# SD_card.net
KiCad netlist of a schematic drawn in Altium Designer
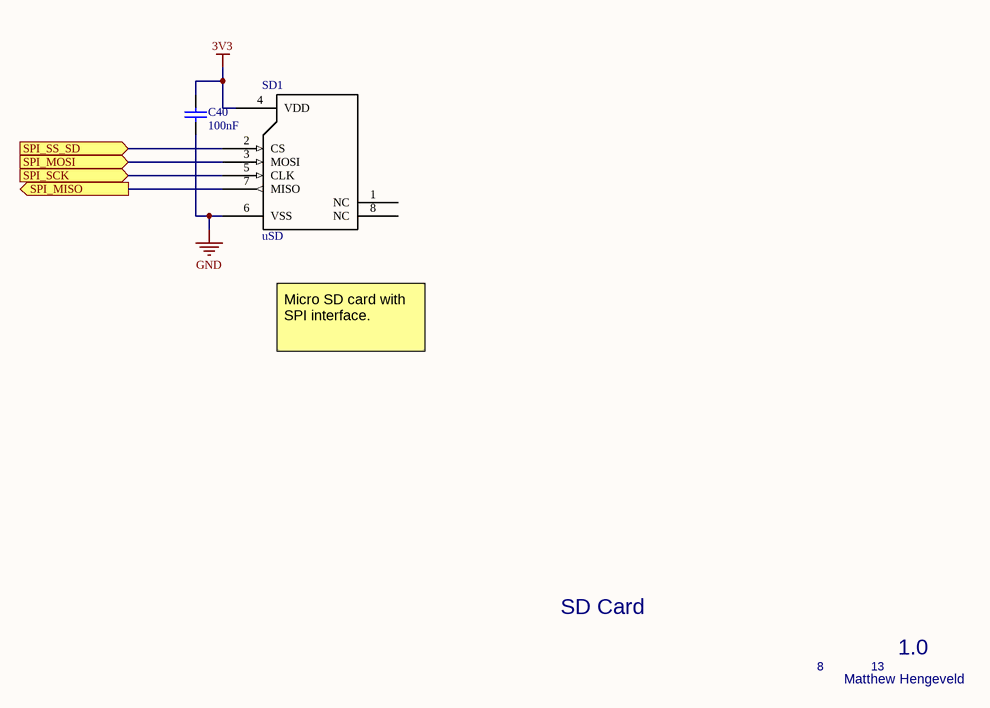
[diagram p0: SD card.SchDoc]

(export (version "E")
  (design (tool "Eeschema 10.0.6"))
  (components
    (comp (ref "C40")
      (value "100nF")
      (footprint "CAPC1608X92X38LL15T08")
      (fields (field (name "PART NUMBER") "VJ0603Y104KNXAO") (field (name "MANUFACTURER") "Vitramon"))
      (libsource (lib "Altium Content Vault") (part "CAP"))
    )
    (comp (ref "SD1")
      (value "uSD")
      (footprint "uSD")
      (description "uSD Card Holder, SPI Interface")
      (libsource (lib "Hengeveld") (part "MicroSD Holder"))
    )
  )
  (nets
    (net (code "1") (name "/SPI_MISO") (class "Default")
      (node (ref "SD1") (pin "7") (pinfunction "MISO_7") (pintype "output"))
    )
    (net (code "2") (name "/SPI_MOSI") (class "Default")
      (node (ref "SD1") (pin "3") (pinfunction "MOSI_3") (pintype "input"))
    )
    (net (code "3") (name "/SPI_SCK") (class "Default")
      (node (ref "SD1") (pin "5") (pinfunction "CLK_5") (pintype "input"))
    )
    (net (code "4") (name "/SPI_SS_SD") (class "Default")
      (node (ref "SD1") (pin "2") (pinfunction "CS_2") (pintype "input"))
    )
    (net (code "5") (name "3V3") (class "Default")
      (node (ref "C40") (pin "2") (pinfunction "2_2") (pintype "passive"))
      (node (ref "SD1") (pin "4") (pinfunction "VDD_4") (pintype "power_in"))
    )
    (net (code "6") (name "GND") (class "Default")
      (node (ref "C40") (pin "1") (pinfunction "1_1") (pintype "passive"))
      (node (ref "SD1") (pin "6") (pinfunction "VSS_6") (pintype "power_in"))
    )
    (net (code "7") (name "unconnected-(SD1-NC-Pad1)") (class "Default")
      (node (ref "SD1") (pin "1") (pinfunction "NC_1") (pintype "passive"))
    )
    (net (code "8") (name "unconnected-(SD1-NC-Pad8)") (class "Default")
      (node (ref "SD1") (pin "8") (pinfunction "NC_8") (pintype "passive"))
    )
  )
)
